# schematic_gprs_old.net
KiCad netlist of a schematic drawn in EAGLE
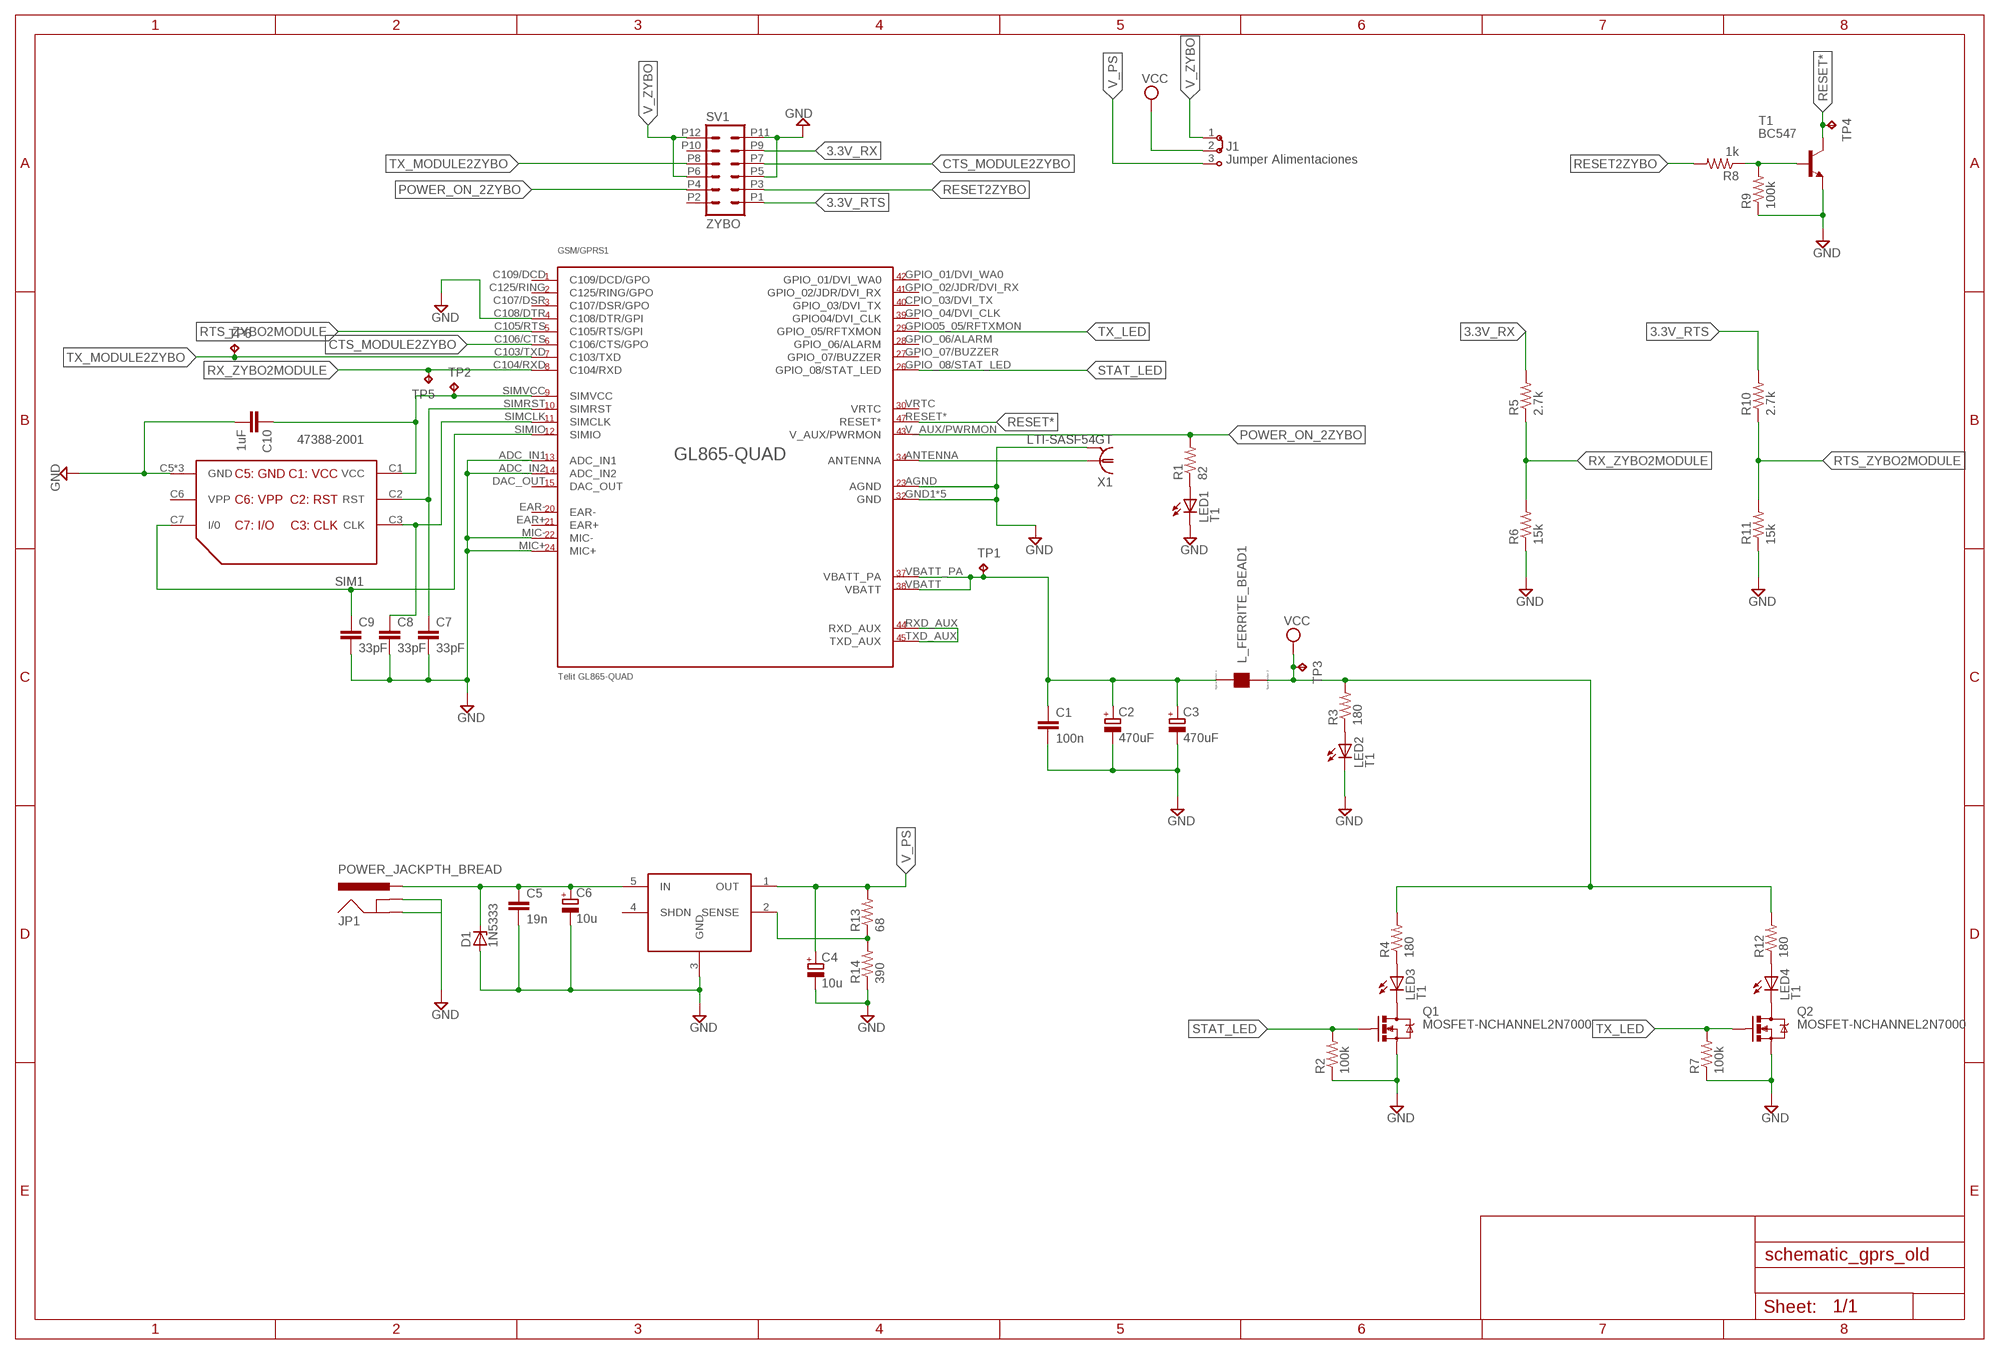
[diagram p0: schematic, sheet 1]

(export (version "E")
  (design (tool "Eeschema 10.0.6"))
  (components
    (comp (ref "C1")
      (value "100n")
      (footprint "eagle-import:C2.5-2")
      (libsource (lib "eagle-import") (part "C2.5/2"))
    )
    (comp (ref "C2")
      (value "470uF")
      (footprint "eagle-import:E3,5-8")
      (libsource (lib "eagle-import") (part "CPOL-EUE3.5-8"))
    )
    (comp (ref "C3")
      (value "470uF")
      (footprint "eagle-import:E3,5-8")
      (libsource (lib "eagle-import") (part "CPOL-EUE3.5-8"))
    )
    (comp (ref "C4")
      (value "10u")
      (footprint "eagle-import:E2-5")
      (libsource (lib "eagle-import") (part "CPOL-EUE2-5"))
    )
    (comp (ref "C5")
      (value "19n")
      (footprint "eagle-import:C050-025X075")
      (libsource (lib "eagle-import") (part "resistor_C-EU050-025X075"))
    )
    (comp (ref "C6")
      (value "10u")
      (footprint "eagle-import:E1,8-4")
      (libsource (lib "eagle-import") (part "CPOL-EUE1.8-4"))
    )
    (comp (ref "C7")
      (value "33pF")
      (footprint "eagle-import:C025-024X044")
      (libsource (lib "eagle-import") (part "C-EU025-024X044"))
    )
    (comp (ref "C8")
      (value "33pF")
      (footprint "eagle-import:C025-024X044")
      (libsource (lib "eagle-import") (part "C-EU025-024X044"))
    )
    (comp (ref "C9")
      (value "33pF")
      (footprint "eagle-import:C025-024X044")
      (libsource (lib "eagle-import") (part "C-EU025-024X044"))
    )
    (comp (ref "C10")
      (value "1uF")
      (footprint "eagle-import:CAP-PTH-SMALL-KIT")
      (libsource (lib "eagle-import") (part "CAPKIT"))
    )
    (comp (ref "D1")
      (value "1N5333")
      (footprint "eagle-import:C1702-15")
      (libsource (lib "eagle-import") (part "1N5333"))
    )
    (comp (ref "GSM/GPRS1")
      (value "Telit GL865-QUAD")
      (footprint "eagle-import:GL865-QUAD")
      (libsource (lib "eagle-import") (part "GL865-QUAD"))
    )
    (comp (ref "J1")
      (value "Jumper Alimentaciones")
      (footprint "eagle-import:04C")
      (libsource (lib "eagle-import") (part "J2X2MM"))
    )
    (comp (ref "JP1")
      (value "POWER_JACKPTH_BREAD")
      (footprint "eagle-import:POWER_JACK_PTH_BREAD")
      (libsource (lib "eagle-import") (part "POWER_JACKPTH_BREAD"))
    )
    (comp (ref "LED1")
      (value "T1")
      (footprint "eagle-import:LED3MM")
      (libsource (lib "eagle-import") (part "LED3MM"))
    )
    (comp (ref "LED2")
      (value "T1")
      (footprint "eagle-import:LED3MM")
      (libsource (lib "eagle-import") (part "LED3MM"))
    )
    (comp (ref "LED3")
      (value "T1")
      (footprint "eagle-import:LED3MM")
      (libsource (lib "eagle-import") (part "LED3MM"))
    )
    (comp (ref "LED4")
      (value "T1")
      (footprint "eagle-import:LED3MM")
      (libsource (lib "eagle-import") (part "LED3MM"))
    )
    (comp (ref "L_FERRITE_BEAD1")
      (value "FERRITEBEAD2")
      (footprint "eagle-import:0207_7")
      (libsource (lib "eagle-import") (part "FERRITEBEAD2"))
    )
    (comp (ref "Q1")
      (value "MOSFET-NCHANNEL2N7000")
      (footprint "eagle-import:TO-92")
      (libsource (lib "eagle-import") (part "MOSFET-NCHANNEL2N7000"))
    )
    (comp (ref "Q2")
      (value "MOSFET-NCHANNEL2N7000")
      (footprint "eagle-import:TO-92")
      (libsource (lib "eagle-import") (part "MOSFET-NCHANNEL2N7000"))
    )
    (comp (ref "R1")
      (value "82")
      (footprint "eagle-import:0207_7")
      (libsource (lib "eagle-import") (part "R-US_0207/7"))
    )
    (comp (ref "R2")
      (value "100k")
      (footprint "eagle-import:0207_7")
      (libsource (lib "eagle-import") (part "R-US_0207/7"))
    )
    (comp (ref "R3")
      (value "180")
      (footprint "eagle-import:0207_7")
      (libsource (lib "eagle-import") (part "R-US_0207/7"))
    )
    (comp (ref "R4")
      (value "180")
      (footprint "eagle-import:0207_7")
      (libsource (lib "eagle-import") (part "R-US_0207/7"))
    )
    (comp (ref "R5")
      (value "2.7k")
      (footprint "eagle-import:0207_7")
      (libsource (lib "eagle-import") (part "R-US_0207/7"))
    )
    (comp (ref "R6")
      (value "15k")
      (footprint "eagle-import:0207_7")
      (libsource (lib "eagle-import") (part "R-US_0207/7"))
    )
    (comp (ref "R7")
      (value "100k")
      (footprint "eagle-import:0207_7")
      (libsource (lib "eagle-import") (part "R-US_0207/7"))
    )
    (comp (ref "R8")
      (value "1k")
      (footprint "eagle-import:0207_7")
      (libsource (lib "eagle-import") (part "R-US_0207/7"))
    )
    (comp (ref "R9")
      (value "100k")
      (footprint "eagle-import:0207_7")
      (libsource (lib "eagle-import") (part "R-US_0207/7"))
    )
    (comp (ref "R10")
      (value "2.7k")
      (footprint "eagle-import:0207_7")
      (libsource (lib "eagle-import") (part "R-US_0207/7"))
    )
    (comp (ref "R11")
      (value "15k")
      (footprint "eagle-import:0207_7")
      (libsource (lib "eagle-import") (part "R-US_0207/7"))
    )
    (comp (ref "R12")
      (value "180")
      (footprint "eagle-import:0207_7")
      (libsource (lib "eagle-import") (part "R-US_0207/7"))
    )
    (comp (ref "R13")
      (value "68")
      (footprint "eagle-import:0207_7")
      (libsource (lib "eagle-import") (part "R-US_0207/7"))
    )
    (comp (ref "R14")
      (value "390")
      (footprint "eagle-import:0207_7")
      (libsource (lib "eagle-import") (part "R-US_0207/7"))
    )
    (comp (ref "SIM1")
      (value "47388-2001")
      (footprint "eagle-import:47388-2001")
      (libsource (lib "eagle-import") (part "47388-2001"))
    )
    (comp (ref "SV1")
      (value "ZYBO")
      (footprint "eagle-import:MA06-2")
      (libsource (lib "eagle-import") (part "MA06-2"))
    )
    (comp (ref "T1")
      (value "BC547")
      (footprint "eagle-import:TO92")
      (libsource (lib "eagle-import") (part "BC547"))
    )
    (comp (ref "TP1")
      (value "TPPAD1-13")
      (footprint "eagle-import:P1-13")
      (libsource (lib "eagle-import") (part "TPPAD1-13"))
    )
    (comp (ref "TP2")
      (value "TPPAD1-13")
      (footprint "eagle-import:P1-13")
      (libsource (lib "eagle-import") (part "TPPAD1-13"))
    )
    (comp (ref "TP3")
      (value "TPPAD1-13")
      (footprint "eagle-import:P1-13")
      (libsource (lib "eagle-import") (part "TPPAD1-13"))
    )
    (comp (ref "TP4")
      (value "TPPAD1-13")
      (footprint "eagle-import:P1-13")
      (libsource (lib "eagle-import") (part "TPPAD1-13"))
    )
    (comp (ref "TP5")
      (value "TPPAD1-13")
      (footprint "eagle-import:P1-13")
      (libsource (lib "eagle-import") (part "TPPAD1-13"))
    )
    (comp (ref "TP6")
      (value "TPPAD1-13")
      (footprint "eagle-import:P1-13")
      (libsource (lib "eagle-import") (part "TPPAD1-13"))
    )
    (comp (ref "U$1")
      (value "LT1528")
      (footprint "eagle-import:Q5-DD")
      (libsource (lib "eagle-import") (part "LT1528"))
    )
    (comp (ref "X1")
      (value "LTI-SASF54GT")
      (footprint "eagle-import:LTI-SASF54GT")
      (libsource (lib "eagle-import") (part "LTI-SASF54GT"))
    )
  )
  (nets
    (net (code "1") (name "3.3V_RTS") (class "Default")
      (node (ref "R10") (pin "2") (pinfunction "2_2") (pintype "passive"))
      (node (ref "SV1") (pin "P1") (pinfunction "1_P1") (pintype "passive"))
    )
    (net (code "2") (name "3.3V_RX") (class "Default")
      (node (ref "R5") (pin "2") (pinfunction "2_2") (pintype "passive"))
      (node (ref "SV1") (pin "P9") (pinfunction "9_P9") (pintype "passive"))
    )
    (net (code "3") (name "CTS_MODULE2ZYBO") (class "Default")
      (node (ref "GSM/GPRS1") (pin "C106/CTS") (pinfunction "C106/CTS/GPO_C106/CTS") (pintype "output"))
      (node (ref "SV1") (pin "P7") (pinfunction "7_P7") (pintype "passive"))
    )
    (net (code "4") (name "GND") (class "Default")
      (node (ref "C1") (pin "2") (pinfunction "2_2") (pintype "passive"))
      (node (ref "C10") (pin "2") (pinfunction "2_2") (pintype "passive"))
      (node (ref "C2") (pin "-") (pinfunction "-_-") (pintype "passive"))
      (node (ref "C3") (pin "-") (pinfunction "-_-") (pintype "passive"))
      (node (ref "C4") (pin "-") (pinfunction "-_-") (pintype "passive"))
      (node (ref "C5") (pin "2") (pinfunction "2_2") (pintype "passive"))
      (node (ref "C6") (pin "-") (pinfunction "-_-") (pintype "passive"))
      (node (ref "C7") (pin "2") (pinfunction "2_2") (pintype "passive"))
      (node (ref "C8") (pin "2") (pinfunction "2_2") (pintype "passive"))
      (node (ref "C9") (pin "2") (pinfunction "2_2") (pintype "passive"))
      (node (ref "D1") (pin "A") (pinfunction "A_A") (pintype "passive"))
      (node (ref "GSM/GPRS1") (pin "ADC_IN1") (pinfunction "ADC_IN1_ADC_IN1") (pintype "input"))
      (node (ref "GSM/GPRS1") (pin "ADC_IN2") (pinfunction "ADC_IN2_ADC_IN2") (pintype "input"))
      (node (ref "GSM/GPRS1") (pin "AGND") (pinfunction "AGND_AGND") (pintype "power_in"))
      (node (ref "GSM/GPRS1") (pin "C108/DTR") (pinfunction "C108/DTR/GPI_C108/DTR") (pintype "input"))
      (node (ref "GSM/GPRS1") (pin "GND1") (pinfunction "GND_GND1") (pintype "power_in"))
      (node (ref "GSM/GPRS1") (pin "GND2") (pinfunction "GND_GND2") (pintype "power_in"))
      (node (ref "GSM/GPRS1") (pin "GND3") (pinfunction "GND_GND3") (pintype "power_in"))
      (node (ref "GSM/GPRS1") (pin "GND4") (pinfunction "GND_GND4") (pintype "power_in"))
      (node (ref "GSM/GPRS1") (pin "GND5") (pinfunction "GND_GND5") (pintype "power_in"))
      (node (ref "GSM/GPRS1") (pin "MIC+") (pinfunction "MIC+_MIC+") (pintype "input"))
      (node (ref "GSM/GPRS1") (pin "MIC-") (pinfunction "MIC-_MIC-") (pintype "input"))
      (node (ref "JP1") (pin "GND") (pinfunction "GND_GND") (pintype "bidirectional"))
      (node (ref "JP1") (pin "GNDBREAK") (pinfunction "GNDBREAK_GNDBREAK") (pintype "bidirectional"))
      (node (ref "LED1") (pin "K") (pinfunction "C_K") (pintype "passive"))
      (node (ref "LED2") (pin "K") (pinfunction "C_K") (pintype "passive"))
      (node (ref "Q1") (pin "1") (pinfunction "S_1") (pintype "passive"))
      (node (ref "Q2") (pin "1") (pinfunction "S_1") (pintype "passive"))
      (node (ref "R11") (pin "1") (pinfunction "1_1") (pintype "passive"))
      (node (ref "R14") (pin "1") (pinfunction "1_1") (pintype "passive"))
      (node (ref "R2") (pin "1") (pinfunction "1_1") (pintype "passive"))
      (node (ref "R6") (pin "1") (pinfunction "1_1") (pintype "passive"))
      (node (ref "R7") (pin "1") (pinfunction "1_1") (pintype "passive"))
      (node (ref "R9") (pin "1") (pinfunction "1_1") (pintype "passive"))
      (node (ref "SIM1") (pin "C5") (pinfunction "GND_C5") (pintype "power_in"))
      (node (ref "SIM1") (pin "GND1") (pinfunction "GND_GND1") (pintype "power_in"))
      (node (ref "SIM1") (pin "GND2") (pinfunction "GND_GND2") (pintype "power_in"))
      (node (ref "SV1") (pin "P11") (pinfunction "11_P11") (pintype "passive"))
      (node (ref "SV1") (pin "P5") (pinfunction "5_P5") (pintype "passive"))
      (node (ref "T1") (pin "1") (pinfunction "E_1") (pintype "passive"))
      (node (ref "U$1") (pin "3") (pinfunction "GND_3") (pintype "bidirectional"))
      (node (ref "X1") (pin "2") (pinfunction "2_2") (pintype "passive"))
      (node (ref "X1") (pin "3") (pinfunction "2_3") (pintype "passive"))
      (node (ref "X1") (pin "4") (pinfunction "2_4") (pintype "passive"))
      (node (ref "X1") (pin "5") (pinfunction "2_5") (pintype "passive"))
    )
    (net (code "5") (name "Net-(GSM/GPRS1-PadANTENNA)") (class "Default")
      (node (ref "GSM/GPRS1") (pin "ANTENNA") (pinfunction "ANTENNA_ANTENNA") (pintype "output"))
      (node (ref "X1") (pin "1") (pinfunction "1_1") (pintype "passive"))
    )
    (net (code "6") (name "Net-(GSM/GPRS1-PadRXD_AUX)") (class "Default")
      (node (ref "GSM/GPRS1") (pin "RXD_AUX") (pinfunction "RXD_AUX_RXD_AUX") (pintype "input"))
      (node (ref "GSM/GPRS1") (pin "TXD_AUX") (pinfunction "TXD_AUX_TXD_AUX") (pintype "output"))
    )
    (net (code "7") (name "Net-(LED1-PadA)") (class "Default")
      (node (ref "LED1") (pin "A") (pinfunction "A_A") (pintype "passive"))
      (node (ref "R1") (pin "1") (pinfunction "1_1") (pintype "passive"))
    )
    (net (code "8") (name "Net-(LED2-PadA)") (class "Default")
      (node (ref "LED2") (pin "A") (pinfunction "A_A") (pintype "passive"))
      (node (ref "R3") (pin "1") (pinfunction "1_1") (pintype "passive"))
    )
    (net (code "9") (name "Net-(LED3-C)") (class "Default")
      (node (ref "LED3") (pin "K") (pinfunction "C_K") (pintype "passive"))
      (node (ref "Q1") (pin "3") (pinfunction "D_3") (pintype "passive"))
    )
    (net (code "10") (name "Net-(LED3-PadA)") (class "Default")
      (node (ref "LED3") (pin "A") (pinfunction "A_A") (pintype "passive"))
      (node (ref "R4") (pin "1") (pinfunction "1_1") (pintype "passive"))
    )
    (net (code "11") (name "Net-(LED4-C)") (class "Default")
      (node (ref "LED4") (pin "K") (pinfunction "C_K") (pintype "passive"))
      (node (ref "Q2") (pin "3") (pinfunction "D_3") (pintype "passive"))
    )
    (net (code "12") (name "Net-(LED4-PadA)") (class "Default")
      (node (ref "LED4") (pin "A") (pinfunction "A_A") (pintype "passive"))
      (node (ref "R12") (pin "1") (pinfunction "1_1") (pintype "passive"))
    )
    (net (code "13") (name "Net-(L_FERRITE_BEAD1-A)") (class "Default")
      (node (ref "C1") (pin "1") (pinfunction "1_1") (pintype "passive"))
      (node (ref "C2") (pin "+") (pinfunction "+_+") (pintype "passive"))
      (node (ref "C3") (pin "+") (pinfunction "+_+") (pintype "passive"))
      (node (ref "GSM/GPRS1") (pin "VBATT") (pinfunction "VBATT_VBATT") (pintype "power_in"))
      (node (ref "GSM/GPRS1") (pin "VBATT_PA") (pinfunction "VBATT_PA_VBATT_PA") (pintype "power_in"))
      (node (ref "L_FERRITE_BEAD1") (pin "1") (pinfunction "A_1") (pintype "passive"))
      (node (ref "TP1") (pin "TP") (pinfunction "TP_TP") (pintype "input"))
    )
    (net (code "14") (name "Net-(SIM1-CLK)") (class "Default")
      (node (ref "C8") (pin "1") (pinfunction "1_1") (pintype "passive"))
      (node (ref "GSM/GPRS1") (pin "SIMCLK") (pinfunction "SIMCLK_SIMCLK") (pintype "output"))
      (node (ref "SIM1") (pin "C3") (pinfunction "CLK_C3") (pintype "input"))
    )
    (net (code "15") (name "Net-(SIM1-I{slash}0)") (class "Default")
      (node (ref "C9") (pin "1") (pinfunction "1_1") (pintype "passive"))
      (node (ref "GSM/GPRS1") (pin "SIMIO") (pinfunction "SIMIO_SIMIO") (pintype "bidirectional"))
      (node (ref "SIM1") (pin "C7") (pinfunction "I/0_C7") (pintype "bidirectional"))
    )
    (net (code "16") (name "Net-(SIM1-RST)") (class "Default")
      (node (ref "C7") (pin "1") (pinfunction "1_1") (pintype "passive"))
      (node (ref "GSM/GPRS1") (pin "SIMRST") (pinfunction "SIMRST_SIMRST") (pintype "output"))
      (node (ref "SIM1") (pin "C2") (pinfunction "RST_C2") (pintype "input"))
    )
    (net (code "17") (name "Net-(SIM1-VCC)") (class "Default")
      (node (ref "C10") (pin "1") (pinfunction "1_1") (pintype "passive"))
      (node (ref "GSM/GPRS1") (pin "SIMVCC") (pinfunction "SIMVCC_SIMVCC") (pintype "power_in"))
      (node (ref "SIM1") (pin "C1") (pinfunction "VCC_C1") (pintype "power_in"))
      (node (ref "TP2") (pin "TP") (pinfunction "TP_TP") (pintype "input"))
    )
    (net (code "18") (name "Net-(T1-B)") (class "Default")
      (node (ref "R8") (pin "1") (pinfunction "1_1") (pintype "passive"))
      (node (ref "R9") (pin "2") (pinfunction "2_2") (pintype "passive"))
      (node (ref "T1") (pin "2") (pinfunction "B_2") (pintype "passive"))
    )
    (net (code "19") (name "Net-(U$1-IN)") (class "Default")
      (node (ref "C5") (pin "1") (pinfunction "1_1") (pintype "passive"))
      (node (ref "C6") (pin "+") (pinfunction "+_+") (pintype "passive"))
      (node (ref "D1") (pin "C") (pinfunction "C_C") (pintype "passive"))
      (node (ref "JP1") (pin "PWR") (pinfunction "PWR_PWR") (pintype "bidirectional"))
      (node (ref "U$1") (pin "5") (pinfunction "IN_5") (pintype "bidirectional"))
    )
    (net (code "20") (name "Net-(U$1-SENSE)") (class "Default")
      (node (ref "R13") (pin "1") (pinfunction "1_1") (pintype "passive"))
      (node (ref "R14") (pin "2") (pinfunction "2_2") (pintype "passive"))
      (node (ref "U$1") (pin "2") (pinfunction "SENSE_2") (pintype "bidirectional"))
    )
    (net (code "21") (name "POWER_ON_2ZYBO") (class "Default")
      (node (ref "GSM/GPRS1") (pin "V_AUX/PWRMON") (pinfunction "V_AUX/PWRMON_V_AUX/PWRMON") (pintype "output"))
      (node (ref "R1") (pin "2") (pinfunction "2_2") (pintype "passive"))
      (node (ref "SV1") (pin "P4") (pinfunction "4_P4") (pintype "passive"))
    )
    (net (code "22") (name "RESET*") (class "Default")
      (node (ref "GSM/GPRS1") (pin "RESET*") (pinfunction "RESET*_RESET*") (pintype "input"))
      (node (ref "T1") (pin "3") (pinfunction "C_3") (pintype "passive"))
      (node (ref "TP4") (pin "TP") (pinfunction "TP_TP") (pintype "input"))
    )
    (net (code "23") (name "RESET2ZYBO") (class "Default")
      (node (ref "R8") (pin "2") (pinfunction "2_2") (pintype "passive"))
      (node (ref "SV1") (pin "P3") (pinfunction "3_P3") (pintype "passive"))
    )
    (net (code "24") (name "RTS_ZYBO2MODULE") (class "Default")
      (node (ref "GSM/GPRS1") (pin "C105/RTS") (pinfunction "C105/RTS/GPI_C105/RTS") (pintype "input"))
      (node (ref "R10") (pin "1") (pinfunction "1_1") (pintype "passive"))
      (node (ref "R11") (pin "2") (pinfunction "2_2") (pintype "passive"))
    )
    (net (code "25") (name "RX_ZYBO2MODULE") (class "Default")
      (node (ref "GSM/GPRS1") (pin "C104/RXD") (pinfunction "C104/RXD_C104/RXD") (pintype "output"))
      (node (ref "R5") (pin "1") (pinfunction "1_1") (pintype "passive"))
      (node (ref "R6") (pin "2") (pinfunction "2_2") (pintype "passive"))
      (node (ref "TP5") (pin "TP") (pinfunction "TP_TP") (pintype "input"))
    )
    (net (code "26") (name "STAT_LED") (class "Default")
      (node (ref "GSM/GPRS1") (pin "GPIO_08/STAT_LED") (pinfunction "GPIO_08/STAT_LED_GPIO_08/STAT_LED") (pintype "bidirectional"))
      (node (ref "Q1") (pin "2") (pinfunction "G_2") (pintype "passive"))
      (node (ref "R2") (pin "2") (pinfunction "2_2") (pintype "passive"))
    )
    (net (code "27") (name "TX_LED") (class "Default")
      (node (ref "GSM/GPRS1") (pin "GPIO05_05/RFTXMON") (pinfunction "GPIO_05/RFTXMON_GPIO05_05/RFTXMON") (pintype "bidirectional"))
      (node (ref "Q2") (pin "2") (pinfunction "G_2") (pintype "passive"))
      (node (ref "R7") (pin "2") (pinfunction "2_2") (pintype "passive"))
    )
    (net (code "28") (name "TX_MODULE2ZYBO") (class "Default")
      (node (ref "GSM/GPRS1") (pin "C103/TXD") (pinfunction "C103/TXD_C103/TXD") (pintype "input"))
      (node (ref "SV1") (pin "P8") (pinfunction "8_P8") (pintype "passive"))
      (node (ref "TP6") (pin "TP") (pinfunction "TP_TP") (pintype "input"))
    )
    (net (code "29") (name "VCC") (class "Default")
      (node (ref "J1") (pin "2") (pinfunction "2_2") (pintype "passive"))
      (node (ref "L_FERRITE_BEAD1") (pin "2") (pinfunction "B_2") (pintype "passive"))
      (node (ref "R12") (pin "2") (pinfunction "2_2") (pintype "passive"))
      (node (ref "R3") (pin "2") (pinfunction "2_2") (pintype "passive"))
      (node (ref "R4") (pin "2") (pinfunction "2_2") (pintype "passive"))
      (node (ref "TP3") (pin "TP") (pinfunction "TP_TP") (pintype "input"))
    )
    (net (code "30") (name "V_PS") (class "Default")
      (node (ref "C4") (pin "+") (pinfunction "+_+") (pintype "passive"))
      (node (ref "J1") (pin "3") (pinfunction "3_3") (pintype "passive"))
      (node (ref "R13") (pin "2") (pinfunction "2_2") (pintype "passive"))
      (node (ref "U$1") (pin "1") (pinfunction "OUT_1") (pintype "bidirectional"))
    )
    (net (code "31") (name "V_ZYBO") (class "Default")
      (node (ref "J1") (pin "1") (pinfunction "1_1") (pintype "passive"))
      (node (ref "SV1") (pin "P12") (pinfunction "12_P12") (pintype "passive"))
      (node (ref "SV1") (pin "P6") (pinfunction "6_P6") (pintype "passive"))
    )
    (net (code "32") (name "unconnected-(GSM/GPRS1-C107{slash}DSR{slash}GPO-PadC107{slash}DSR)") (class "Default")
      (node (ref "GSM/GPRS1") (pin "C107/DSR") (pinfunction "C107/DSR/GPO_C107/DSR") (pintype "output"))
    )
    (net (code "33") (name "unconnected-(GSM/GPRS1-C109{slash}DCD{slash}GPO-PadC109{slash}DCD)") (class "Default")
      (node (ref "GSM/GPRS1") (pin "C109/DCD") (pinfunction "C109/DCD/GPO_C109/DCD") (pintype "output"))
    )
    (net (code "34") (name "unconnected-(GSM/GPRS1-C125{slash}RING{slash}GPO-PadC125{slash}RING)") (class "Default")
      (node (ref "GSM/GPRS1") (pin "C125/RING") (pinfunction "C125/RING/GPO_C125/RING") (pintype "output"))
    )
    (net (code "35") (name "unconnected-(GSM/GPRS1-GPIO04{slash}DVI_CLK-PadGPIO_04{slash}DVI_CLK)") (class "Default")
      (node (ref "GSM/GPRS1") (pin "GPIO_04/DVI_CLK") (pinfunction "GPIO04/DVI_CLK_GPIO_04/DVI_CLK") (pintype "bidirectional"))
    )
    (net (code "36") (name "unconnected-(GSM/GPRS1-GPIO_03{slash}DVI_TX-PadCPIO_03{slash}DVI_TX)") (class "Default")
      (node (ref "GSM/GPRS1") (pin "CPIO_03/DVI_TX") (pinfunction "GPIO_03/DVI_TX_CPIO_03/DVI_TX") (pintype "bidirectional"))
    )
    (net (code "37") (name "unconnected-(GSM/GPRS1-PadDAC_OUT)") (class "Default")
      (node (ref "GSM/GPRS1") (pin "DAC_OUT") (pinfunction "DAC_OUT_DAC_OUT") (pintype "output"))
    )
    (net (code "38") (name "unconnected-(GSM/GPRS1-PadEAR+)") (class "Default")
      (node (ref "GSM/GPRS1") (pin "EAR+") (pinfunction "EAR+_EAR+") (pintype "output"))
    )
    (net (code "39") (name "unconnected-(GSM/GPRS1-PadEAR-)") (class "Default")
      (node (ref "GSM/GPRS1") (pin "EAR-") (pinfunction "EAR-_EAR-") (pintype "output"))
    )
    (net (code "40") (name "unconnected-(GSM/GPRS1-PadGPIO_01{slash}DVI_WA0)") (class "Default")
      (node (ref "GSM/GPRS1") (pin "GPIO_01/DVI_WA0") (pinfunction "GPIO_01/DVI_WA0_GPIO_01/DVI_WA0") (pintype "bidirectional"))
    )
    (net (code "41") (name "unconnected-(GSM/GPRS1-PadGPIO_02{slash}JDR{slash}DVI_RX)") (class "Default")
      (node (ref "GSM/GPRS1") (pin "GPIO_02/JDR/DVI_RX") (pinfunction "GPIO_02/JDR/DVI_RX_GPIO_02/JDR/DVI_RX") (pintype "bidirectional"))
    )
    (net (code "42") (name "unconnected-(GSM/GPRS1-PadGPIO_06{slash}ALARM)") (class "Default")
      (node (ref "GSM/GPRS1") (pin "GPIO_06/ALARM") (pinfunction "GPIO_06/ALARM_GPIO_06/ALARM") (pintype "bidirectional"))
    )
    (net (code "43") (name "unconnected-(GSM/GPRS1-PadGPIO_07{slash}BUZZER)") (class "Default")
      (node (ref "GSM/GPRS1") (pin "GPIO_07/BUZZER") (pinfunction "GPIO_07/BUZZER_GPIO_07/BUZZER") (pintype "bidirectional"))
    )
    (net (code "44") (name "unconnected-(GSM/GPRS1-PadVRTC)") (class "Default")
      (node (ref "GSM/GPRS1") (pin "VRTC") (pinfunction "VRTC_VRTC") (pintype "output"))
    )
    (net (code "45") (name "unconnected-(SIM1-VPP-PadC6)") (class "Default")
      (node (ref "SIM1") (pin "C6") (pinfunction "VPP_C6") (pintype "bidirectional"))
    )
    (net (code "46") (name "unconnected-(SV1-2-PadP2)") (class "Default")
      (node (ref "SV1") (pin "P2") (pinfunction "2_P2") (pintype "passive"))
    )
    (net (code "47") (name "unconnected-(SV1-10-PadP10)") (class "Default")
      (node (ref "SV1") (pin "P10") (pinfunction "10_P10") (pintype "passive"))
    )
    (net (code "48") (name "unconnected-(U$1-SHDN-Pad4)") (class "Default")
      (node (ref "U$1") (pin "4") (pinfunction "SHDN_4") (pintype "bidirectional"))
    )
  )
)
